# Top.net
KiCad netlist of a schematic drawn in Altium Designer
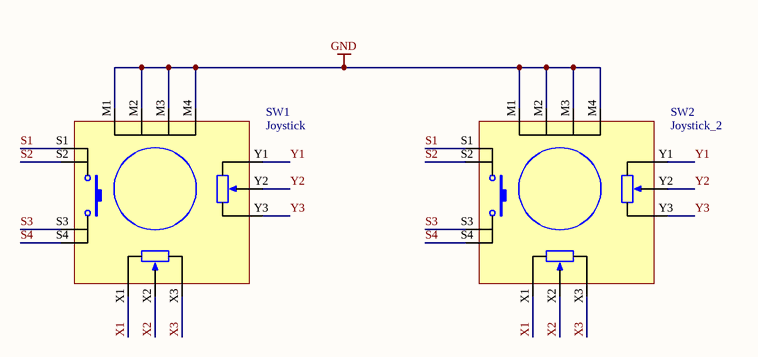
[diagram p0: Top.SchDoc]

(export (version "E")
  (design (tool "Eeschema 10.0.6"))
  (components
    (comp (ref "SW1") (value "Joystick") (footprint "Joystick") (libsource (lib "Common") (part "Joystick")))
    (comp (ref "SW2")
      (value "Joystick_2")
      (footprint "Joystick2")
      (libsource (lib "Common") (part "Joystick_2"))
    )
  )
  (nets
    (net (code "1") (name "/S1") (class "Default")
      (node (ref "SW1") (pin "S1") (pinfunction "S1_S1") (pintype "passive"))
      (node (ref "SW2") (pin "S1") (pinfunction "S1_S1") (pintype "passive"))
    )
    (net (code "2") (name "/S2") (class "Default")
      (node (ref "SW1") (pin "S2") (pinfunction "S2_S2") (pintype "passive"))
      (node (ref "SW2") (pin "S2") (pinfunction "S2_S2") (pintype "passive"))
    )
    (net (code "3") (name "/S3") (class "Default")
      (node (ref "SW1") (pin "S3") (pinfunction "S3_S3") (pintype "passive"))
      (node (ref "SW2") (pin "S3") (pinfunction "S3_S3") (pintype "passive"))
    )
    (net (code "4") (name "/S4") (class "Default")
      (node (ref "SW1") (pin "S4") (pinfunction "S4_S4") (pintype "passive"))
      (node (ref "SW2") (pin "S4") (pinfunction "S4_S4") (pintype "passive"))
    )
    (net (code "5") (name "/X1") (class "Default")
      (node (ref "SW1") (pin "X1") (pinfunction "X1_X1") (pintype "passive"))
      (node (ref "SW2") (pin "X1") (pinfunction "X1_X1") (pintype "passive"))
    )
    (net (code "6") (name "/X2") (class "Default")
      (node (ref "SW1") (pin "X2") (pinfunction "X2_X2") (pintype "passive"))
      (node (ref "SW2") (pin "X2") (pinfunction "X2_X2") (pintype "passive"))
    )
    (net (code "7") (name "/X3") (class "Default")
      (node (ref "SW1") (pin "X3") (pinfunction "X3_X3") (pintype "passive"))
      (node (ref "SW2") (pin "X3") (pinfunction "X3_X3") (pintype "passive"))
    )
    (net (code "8") (name "/Y1") (class "Default")
      (node (ref "SW1") (pin "Y1") (pinfunction "Y1_Y1") (pintype "passive"))
      (node (ref "SW2") (pin "Y1") (pinfunction "Y1_Y1") (pintype "passive"))
    )
    (net (code "9") (name "/Y2") (class "Default")
      (node (ref "SW1") (pin "Y2") (pinfunction "Y2_Y2") (pintype "passive"))
      (node (ref "SW2") (pin "Y2") (pinfunction "Y2_Y2") (pintype "passive"))
    )
    (net (code "10") (name "/Y3") (class "Default")
      (node (ref "SW1") (pin "Y3") (pinfunction "Y3_Y3") (pintype "passive"))
      (node (ref "SW2") (pin "Y3") (pinfunction "Y3_Y3") (pintype "passive"))
    )
    (net (code "11") (name "GND") (class "Default")
      (node (ref "SW1") (pin "M1") (pinfunction "M1_M1") (pintype "passive"))
      (node (ref "SW1") (pin "M2") (pinfunction "M2_M2") (pintype "passive"))
      (node (ref "SW1") (pin "M3") (pinfunction "M3_M3") (pintype "passive"))
      (node (ref "SW1") (pin "M4") (pinfunction "M4_M4") (pintype "passive"))
      (node (ref "SW2") (pin "M1") (pinfunction "M1_M1") (pintype "passive"))
      (node (ref "SW2") (pin "M2") (pinfunction "M2_M2") (pintype "passive"))
      (node (ref "SW2") (pin "M3") (pinfunction "M3_M3") (pintype "passive"))
      (node (ref "SW2") (pin "M4") (pinfunction "M4_M4") (pintype "passive"))
    )
  )
)
